# RS485.net
KiCad netlist of a schematic drawn in Altium Designer
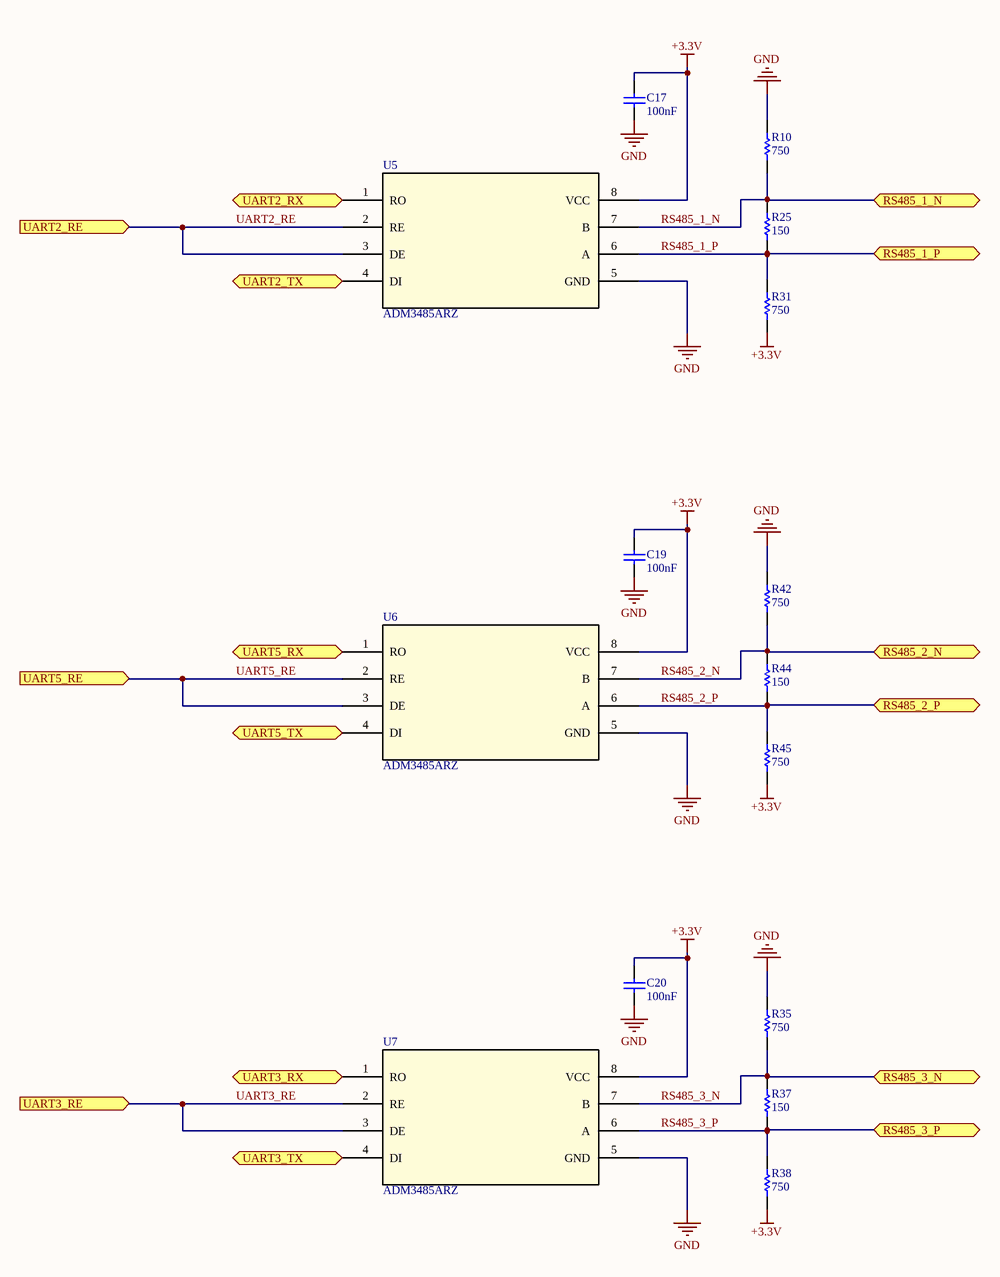
[diagram p0: RS485.SchDoc]

(export (version "E")
  (design (tool "Eeschema 10.0.6"))
  (components
    (comp (ref "C17")
      (value "100nF")
      (footprint "C-805")
      (description "Capacitor")
      (fields (field (name "Comment") "C-805") (field (name "PUBLISHER") "Altium Limited"))
      (libsource (lib "AfraLIB") (part "C-805"))
    )
    (comp (ref "C19")
      (value "100nF")
      (footprint "C-805")
      (description "Capacitor")
      (fields (field (name "Comment") "C-805") (field (name "PUBLISHER") "Altium Limited"))
      (libsource (lib "AfraLIB") (part "C-805"))
    )
    (comp (ref "C20")
      (value "100nF")
      (footprint "C-805")
      (description "Capacitor")
      (fields (field (name "Comment") "C-805") (field (name "PUBLISHER") "Altium Limited"))
      (libsource (lib "AfraLIB") (part "C-805"))
    )
    (comp (ref "R10")
      (value "750")
      (footprint "R-805")
      (description "Resistor")
      (fields (field (name "Comment") "R-805"))
      (libsource (lib "AfraLIB") (part "R-805"))
    )
    (comp (ref "R25")
      (value "150")
      (footprint "R-805")
      (description "Resistor")
      (fields (field (name "Comment") "R-805"))
      (libsource (lib "AfraLIB") (part "R-805"))
    )
    (comp (ref "R31")
      (value "750")
      (footprint "R-805")
      (description "Resistor")
      (fields (field (name "Comment") "R-805"))
      (libsource (lib "AfraLIB") (part "R-805"))
    )
    (comp (ref "R35")
      (value "750")
      (footprint "R-805")
      (description "Resistor")
      (fields (field (name "Comment") "R-805"))
      (libsource (lib "AfraLIB") (part "R-805"))
    )
    (comp (ref "R37")
      (value "150")
      (footprint "R-805")
      (description "Resistor")
      (fields (field (name "Comment") "R-805"))
      (libsource (lib "AfraLIB") (part "R-805"))
    )
    (comp (ref "R38")
      (value "750")
      (footprint "R-805")
      (description "Resistor")
      (fields (field (name "Comment") "R-805"))
      (libsource (lib "AfraLIB") (part "R-805"))
    )
    (comp (ref "R42")
      (value "750")
      (footprint "R-805")
      (description "Resistor")
      (fields (field (name "Comment") "R-805"))
      (libsource (lib "AfraLIB") (part "R-805"))
    )
    (comp (ref "R44")
      (value "150")
      (footprint "R-805")
      (description "Resistor")
      (fields (field (name "Comment") "R-805"))
      (libsource (lib "AfraLIB") (part "R-805"))
    )
    (comp (ref "R45")
      (value "750")
      (footprint "R-805")
      (description "Resistor")
      (fields (field (name "Comment") "R-805"))
      (libsource (lib "AfraLIB") (part "R-805"))
    )
    (comp (ref "U5")
      (value "ADM3485ARZ")
      (footprint "R_8")
      (description "No Description Available")
      (fields (field (name "COPYRIGHT") "Copyright (C) 2018 Accelerated Designs. All rights reserved"))
      (libsource (lib "AfraLIB") (part "ADM3485ARZ"))
    )
    (comp (ref "U6")
      (value "ADM3485ARZ")
      (footprint "R_8")
      (description "No Description Available")
      (fields (field (name "COPYRIGHT") "Copyright (C) 2018 Accelerated Designs. All rights reserved"))
      (libsource (lib "AfraLIB") (part "ADM3485ARZ"))
    )
    (comp (ref "U7")
      (value "ADM3485ARZ")
      (footprint "R_8")
      (description "No Description Available")
      (fields (field (name "COPYRIGHT") "Copyright (C) 2018 Accelerated Designs. All rights reserved"))
      (libsource (lib "AfraLIB") (part "ADM3485ARZ"))
    )
  )
  (nets
    (net (code "1") (name "+3.3V") (class "Default")
      (node (ref "C17") (pin "2") (pinfunction "2_2") (pintype "passive"))
      (node (ref "C19") (pin "2") (pinfunction "2_2") (pintype "passive"))
      (node (ref "C20") (pin "2") (pinfunction "2_2") (pintype "passive"))
      (node (ref "R31") (pin "1") (pinfunction "1_1") (pintype "passive"))
      (node (ref "R38") (pin "1") (pinfunction "1_1") (pintype "passive"))
      (node (ref "R45") (pin "1") (pinfunction "1_1") (pintype "passive"))
      (node (ref "U5") (pin "8") (pinfunction "VCC_8") (pintype "passive"))
      (node (ref "U6") (pin "8") (pinfunction "VCC_8") (pintype "passive"))
      (node (ref "U7") (pin "8") (pinfunction "VCC_8") (pintype "passive"))
    )
    (net (code "2") (name "/RS485_1_N") (class "Default")
      (node (ref "R10") (pin "1") (pinfunction "1_1") (pintype "passive"))
      (node (ref "R25") (pin "2") (pinfunction "2_2") (pintype "passive"))
      (node (ref "U5") (pin "7") (pinfunction "B_7") (pintype "passive"))
    )
    (net (code "3") (name "/RS485_1_P") (class "Default")
      (node (ref "R25") (pin "1") (pinfunction "1_1") (pintype "passive"))
      (node (ref "R31") (pin "2") (pinfunction "2_2") (pintype "passive"))
      (node (ref "U5") (pin "6") (pinfunction "A_6") (pintype "passive"))
    )
    (net (code "4") (name "/RS485_2_N") (class "Default")
      (node (ref "R42") (pin "1") (pinfunction "1_1") (pintype "passive"))
      (node (ref "R44") (pin "2") (pinfunction "2_2") (pintype "passive"))
      (node (ref "U6") (pin "7") (pinfunction "B_7") (pintype "passive"))
    )
    (net (code "5") (name "/RS485_2_P") (class "Default")
      (node (ref "R44") (pin "1") (pinfunction "1_1") (pintype "passive"))
      (node (ref "R45") (pin "2") (pinfunction "2_2") (pintype "passive"))
      (node (ref "U6") (pin "6") (pinfunction "A_6") (pintype "passive"))
    )
    (net (code "6") (name "/RS485_3_N") (class "Default")
      (node (ref "R35") (pin "1") (pinfunction "1_1") (pintype "passive"))
      (node (ref "R37") (pin "2") (pinfunction "2_2") (pintype "passive"))
      (node (ref "U7") (pin "7") (pinfunction "B_7") (pintype "passive"))
    )
    (net (code "7") (name "/RS485_3_P") (class "Default")
      (node (ref "R37") (pin "1") (pinfunction "1_1") (pintype "passive"))
      (node (ref "R38") (pin "2") (pinfunction "2_2") (pintype "passive"))
      (node (ref "U7") (pin "6") (pinfunction "A_6") (pintype "passive"))
    )
    (net (code "8") (name "/UART2_RE") (class "Default")
      (node (ref "U5") (pin "2") (pinfunction "RE_2") (pintype "passive"))
      (node (ref "U5") (pin "3") (pinfunction "DE_3") (pintype "passive"))
    )
    (net (code "9") (name "/UART2_RX") (class "Default")
      (node (ref "U5") (pin "1") (pinfunction "RO_1") (pintype "passive"))
    )
    (net (code "10") (name "/UART2_TX") (class "Default")
      (node (ref "U5") (pin "4") (pinfunction "DI_4") (pintype "passive"))
    )
    (net (code "11") (name "/UART3_RE") (class "Default")
      (node (ref "U7") (pin "2") (pinfunction "RE_2") (pintype "passive"))
      (node (ref "U7") (pin "3") (pinfunction "DE_3") (pintype "passive"))
    )
    (net (code "12") (name "/UART3_RX") (class "Default")
      (node (ref "U7") (pin "1") (pinfunction "RO_1") (pintype "passive"))
    )
    (net (code "13") (name "/UART3_TX") (class "Default")
      (node (ref "U7") (pin "4") (pinfunction "DI_4") (pintype "passive"))
    )
    (net (code "14") (name "/UART5_RE") (class "Default")
      (node (ref "U6") (pin "2") (pinfunction "RE_2") (pintype "passive"))
      (node (ref "U6") (pin "3") (pinfunction "DE_3") (pintype "passive"))
    )
    (net (code "15") (name "/UART5_RX") (class "Default")
      (node (ref "U6") (pin "1") (pinfunction "RO_1") (pintype "passive"))
    )
    (net (code "16") (name "/UART5_TX") (class "Default")
      (node (ref "U6") (pin "4") (pinfunction "DI_4") (pintype "passive"))
    )
    (net (code "17") (name "GND") (class "Default")
      (node (ref "C17") (pin "1") (pinfunction "1_1") (pintype "passive"))
      (node (ref "C19") (pin "1") (pinfunction "1_1") (pintype "passive"))
      (node (ref "C20") (pin "1") (pinfunction "1_1") (pintype "passive"))
      (node (ref "R10") (pin "2") (pinfunction "2_2") (pintype "passive"))
      (node (ref "R35") (pin "2") (pinfunction "2_2") (pintype "passive"))
      (node (ref "R42") (pin "2") (pinfunction "2_2") (pintype "passive"))
      (node (ref "U5") (pin "5") (pinfunction "GND_5") (pintype "passive"))
      (node (ref "U6") (pin "5") (pinfunction "GND_5") (pintype "passive"))
      (node (ref "U7") (pin "5") (pinfunction "GND_5") (pintype "passive"))
    )
  )
)
